# ambika_polivoks.net
KiCad netlist of a schematic drawn in EAGLE
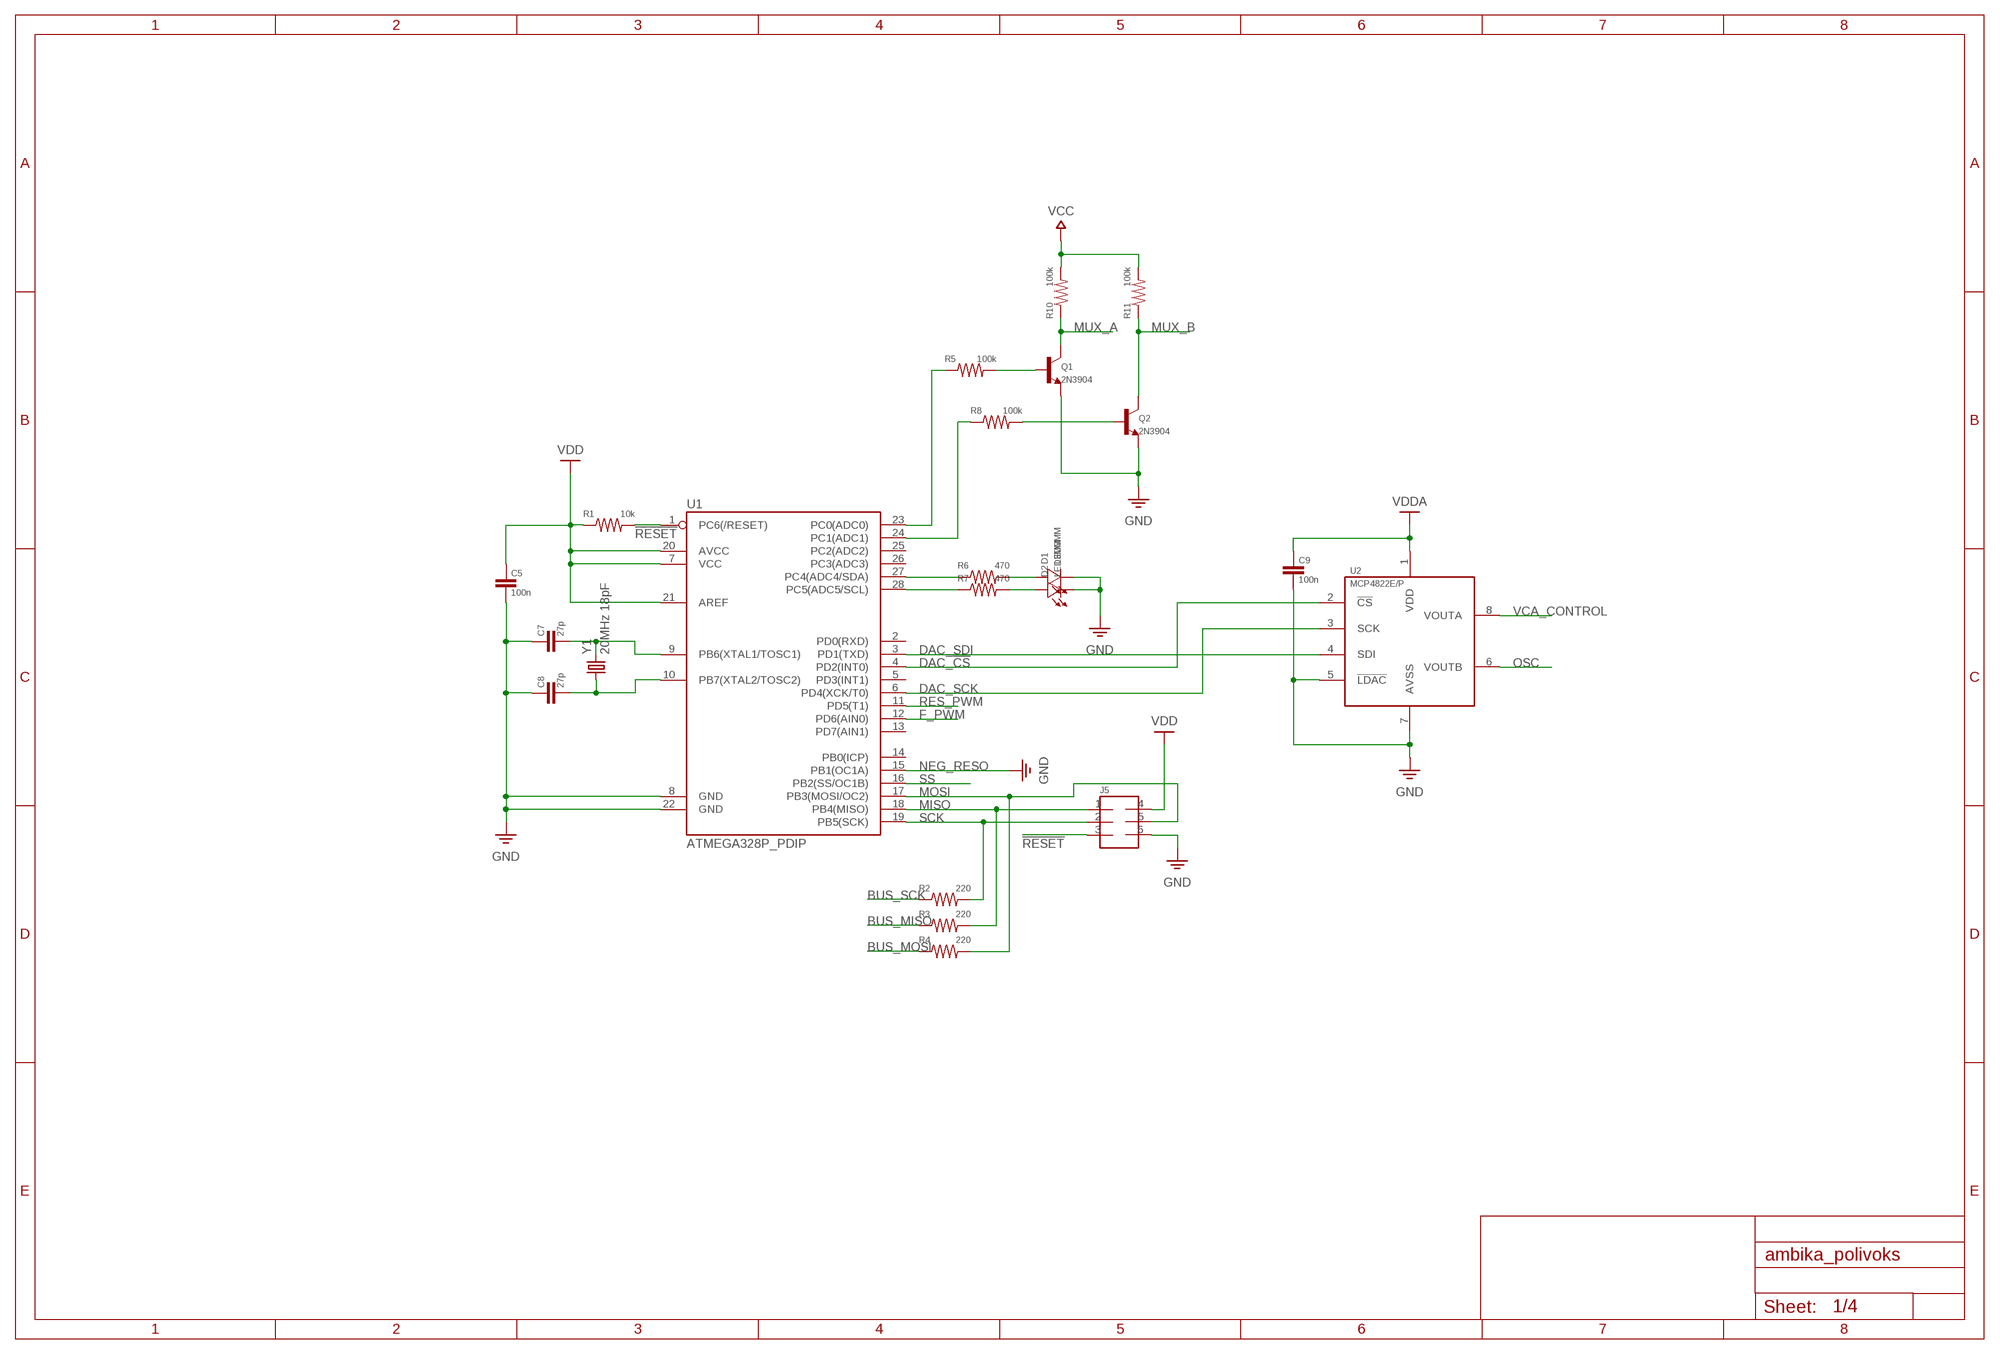
[diagram p0: schematic, sheet 1]
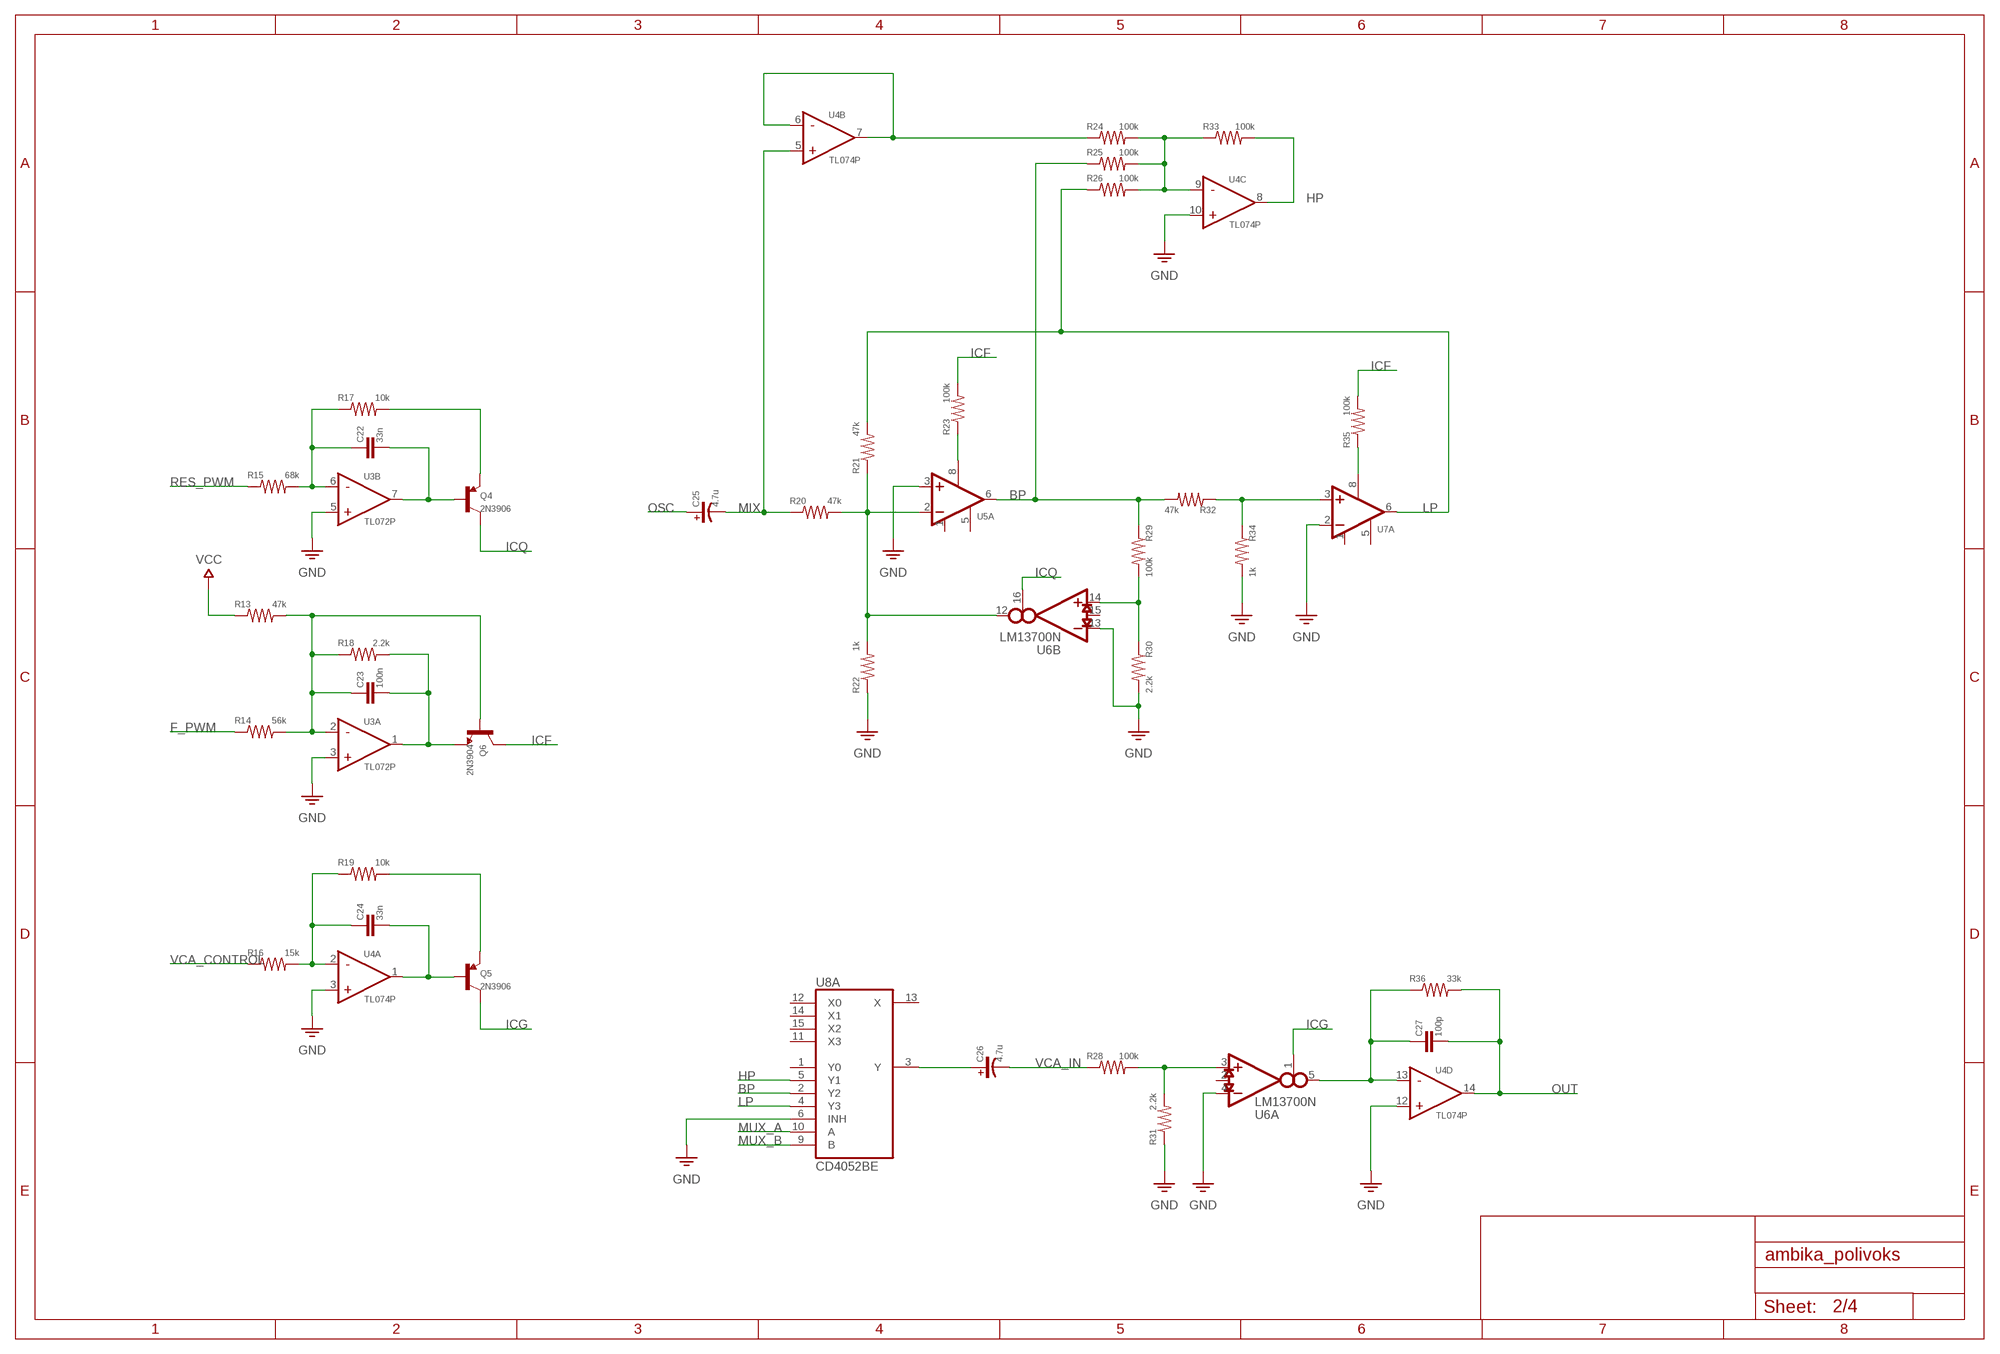
[diagram p1: schematic, sheet 2]
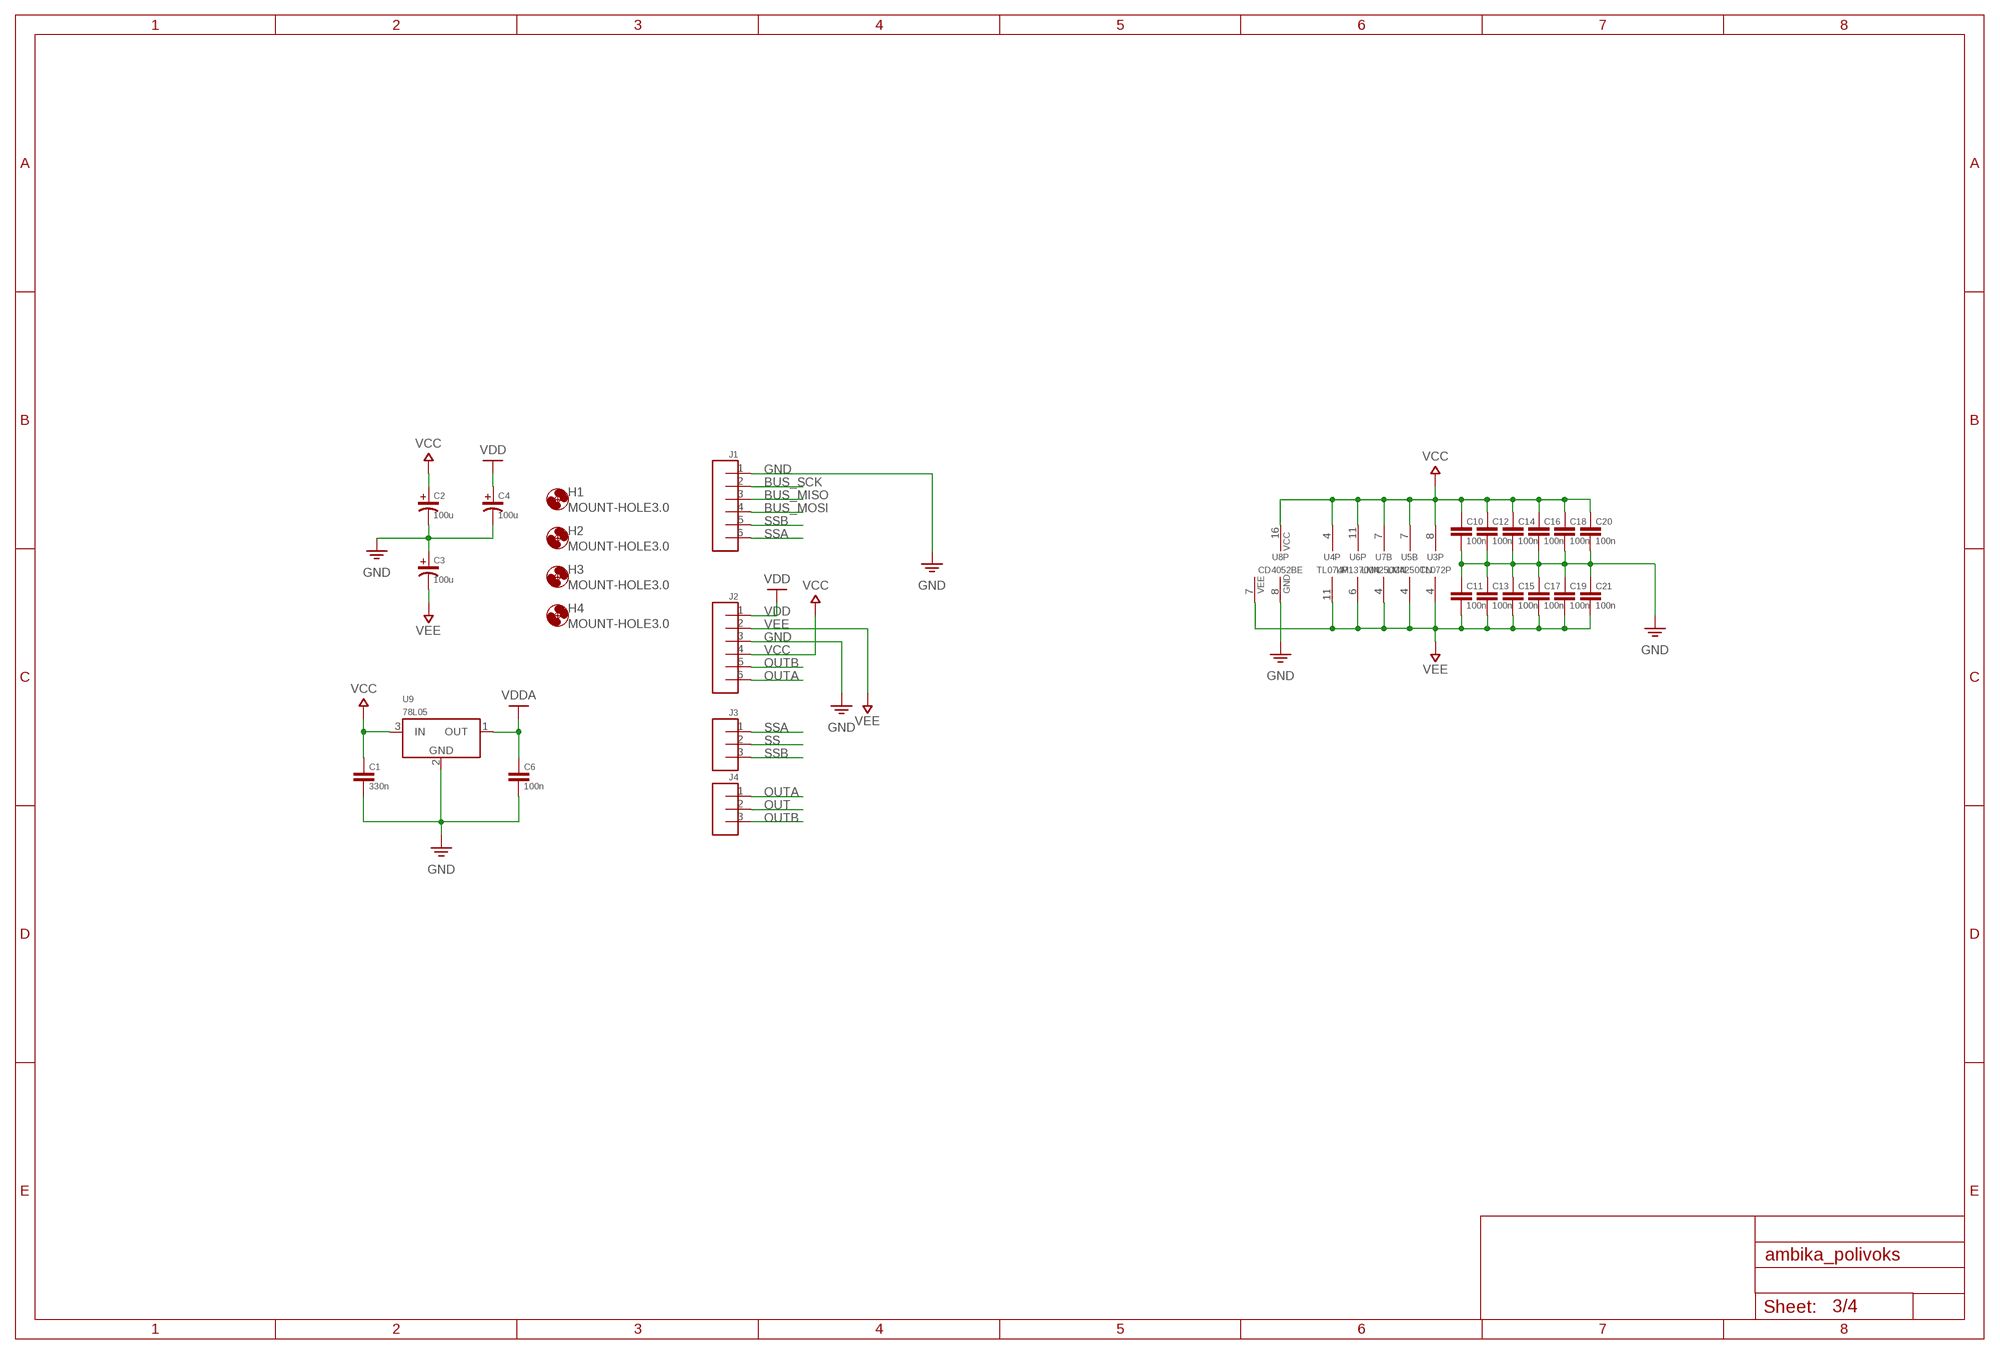
[diagram p2: schematic, sheet 3]
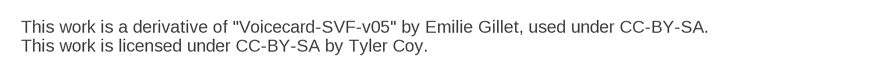
[diagram p3: schematic, sheet 4]

(export (version "E")
  (design (tool "Eeschema 10.0.6"))
  (components
    (comp (ref "C22")
      (value "33n")
      (footprint "eagle-import:CAP_0.1")
      (libsource (lib "eagle-import") (part "CAPACITOR"))
    )
    (comp (ref "C23")
      (value "100n")
      (footprint "eagle-import:CAP_0.1")
      (libsource (lib "eagle-import") (part "CAPACITOR"))
    )
    (comp (ref "C24")
      (value "33n")
      (footprint "eagle-import:CAP_0.1")
      (libsource (lib "eagle-import") (part "CAPACITOR"))
    )
    (comp (ref "C25")
      (value "4.7u")
      (footprint "eagle-import:CAP_ELEC_5MM_2MM_HORZ1")
      (libsource (lib "eagle-import") (part "CAPACITOR_POLARIZED5MM_HORZ1"))
    )
    (comp (ref "C26")
      (value "4.7u")
      (footprint "eagle-import:CAP_ELEC_5MM_2MM_HORZ2")
      (libsource (lib "eagle-import") (part "CAPACITOR_POLARIZED5MM_HORZ2"))
    )
    (comp (ref "C27")
      (value "100p")
      (footprint "eagle-import:CAP_0.1")
      (libsource (lib "eagle-import") (part "CAPACITOR"))
    )
    (comp (ref "Q4")
      (value "2N3906")
      (footprint "eagle-import:TO-92_TRI")
      (libsource (lib "eagle-import") (part "2N3906"))
    )
    (comp (ref "Q5")
      (value "2N3906")
      (footprint "eagle-import:TO-92_TRI")
      (libsource (lib "eagle-import") (part "2N3906"))
    )
    (comp (ref "Q6")
      (value "2N3904")
      (footprint "eagle-import:TO-92_TRI")
      (libsource (lib "eagle-import") (part "2N3904"))
    )
    (comp (ref "R13")
      (value "47k")
      (footprint "eagle-import:RESISTOR_1_4W")
      (libsource (lib "eagle-import") (part "RESISTOR_PTH_1/4W"))
    )
    (comp (ref "R14")
      (value "56k")
      (footprint "eagle-import:RESISTOR_1_4W")
      (libsource (lib "eagle-import") (part "RESISTOR_PTH_1/4W"))
    )
    (comp (ref "R15")
      (value "68k")
      (footprint "eagle-import:RESISTOR_1_4W")
      (libsource (lib "eagle-import") (part "RESISTOR_PTH_1/4W"))
    )
    (comp (ref "R16")
      (value "15k")
      (footprint "eagle-import:RESISTOR_1_4W")
      (libsource (lib "eagle-import") (part "RESISTOR_PTH_1/4W"))
    )
    (comp (ref "R17")
      (value "10k")
      (footprint "eagle-import:RESISTOR_1_4W")
      (libsource (lib "eagle-import") (part "RESISTOR_PTH_1/4W"))
    )
    (comp (ref "R18")
      (value "2.2k")
      (footprint "eagle-import:RESISTOR_1_4W")
      (libsource (lib "eagle-import") (part "RESISTOR_PTH_1/4W"))
    )
    (comp (ref "R19")
      (value "10k")
      (footprint "eagle-import:RESISTOR_1_4W")
      (libsource (lib "eagle-import") (part "RESISTOR_PTH_1/4W"))
    )
    (comp (ref "R20")
      (value "47k")
      (footprint "eagle-import:RESISTOR_1_4W")
      (libsource (lib "eagle-import") (part "RESISTOR_PTH_1/4W"))
    )
    (comp (ref "R21")
      (value "47k")
      (footprint "eagle-import:RESISTOR_1_4W")
      (libsource (lib "eagle-import") (part "RESISTOR_PTH_1/4W"))
    )
    (comp (ref "R22")
      (value "1k")
      (footprint "eagle-import:RESISTOR_1_4W")
      (libsource (lib "eagle-import") (part "RESISTOR_PTH_1/4W"))
    )
    (comp (ref "R23")
      (value "100k")
      (footprint "eagle-import:RESISTOR_1_4W")
      (libsource (lib "eagle-import") (part "RESISTOR_PTH_1/4W"))
    )
    (comp (ref "R24")
      (value "100k")
      (footprint "eagle-import:RESISTOR_1_4W")
      (libsource (lib "eagle-import") (part "RESISTOR_PTH_1/4W"))
    )
    (comp (ref "R25")
      (value "100k")
      (footprint "eagle-import:RESISTOR_1_4W")
      (libsource (lib "eagle-import") (part "RESISTOR_PTH_1/4W"))
    )
    (comp (ref "R26")
      (value "100k")
      (footprint "eagle-import:RESISTOR_1_4W")
      (libsource (lib "eagle-import") (part "RESISTOR_PTH_1/4W"))
    )
    (comp (ref "R28")
      (value "100k")
      (footprint "eagle-import:RESISTOR_1_4W")
      (libsource (lib "eagle-import") (part "RESISTOR_PTH_1/4W"))
    )
    (comp (ref "R29")
      (value "100k")
      (footprint "eagle-import:RESISTOR_1_4W")
      (libsource (lib "eagle-import") (part "RESISTOR_PTH_1/4W"))
    )
    (comp (ref "R30")
      (value "2.2k")
      (footprint "eagle-import:RESISTOR_1_4W")
      (libsource (lib "eagle-import") (part "RESISTOR_PTH_1/4W"))
    )
    (comp (ref "R31")
      (value "2.2k")
      (footprint "eagle-import:RESISTOR_1_4W")
      (libsource (lib "eagle-import") (part "RESISTOR_PTH_1/4W"))
    )
    (comp (ref "R32")
      (value "47k")
      (footprint "eagle-import:RESISTOR_1_4W")
      (libsource (lib "eagle-import") (part "RESISTOR_PTH_1/4W"))
    )
    (comp (ref "R33")
      (value "100k")
      (footprint "eagle-import:RESISTOR_1_4W")
      (libsource (lib "eagle-import") (part "RESISTOR_PTH_1/4W"))
    )
    (comp (ref "R34")
      (value "1k")
      (footprint "eagle-import:RESISTOR_1_4W")
      (libsource (lib "eagle-import") (part "RESISTOR_PTH_1/4W"))
    )
    (comp (ref "R35")
      (value "100k")
      (footprint "eagle-import:RESISTOR_1_4W")
      (libsource (lib "eagle-import") (part "RESISTOR_PTH_1/4W"))
    )
    (comp (ref "R36")
      (value "33k")
      (footprint "eagle-import:RESISTOR_1_4W")
      (libsource (lib "eagle-import") (part "RESISTOR_PTH_1/4W"))
    )
    (comp (ref "U3")
      (value "TL072P")
      (footprint "eagle-import:DIP8")
      (libsource (lib "eagle-import") (part "TL072P"))
    )
    (comp (ref "U4")
      (value "TL074P")
      (footprint "eagle-import:DIP14")
      (libsource (lib "eagle-import") (part "TL074P"))
    )
    (comp (ref "U5")
      (value "LM4250CN")
      (footprint "eagle-import:DIP8")
      (libsource (lib "eagle-import") (part "LM4250CN"))
    )
    (comp (ref "U6")
      (value "LM13700N")
      (footprint "eagle-import:DIP16")
      (libsource (lib "eagle-import") (part "LM13700N"))
    )
    (comp (ref "U7")
      (value "LM4250CN")
      (footprint "eagle-import:DIP8")
      (libsource (lib "eagle-import") (part "LM4250CN"))
    )
    (comp (ref "U8")
      (value "CD4052BE")
      (footprint "eagle-import:DIP16")
      (libsource (lib "eagle-import") (part "CD4052BE"))
    )
    (comp (ref "C5")
      (value "100n")
      (footprint "eagle-import:CAP_0.1")
      (libsource (lib "eagle-import") (part "CAPACITOR"))
    )
    (comp (ref "C7")
      (value "27p")
      (footprint "eagle-import:CAP_0.1")
      (libsource (lib "eagle-import") (part "CAPACITOR"))
    )
    (comp (ref "C8")
      (value "27p")
      (footprint "eagle-import:CAP_0.1")
      (libsource (lib "eagle-import") (part "CAPACITOR"))
    )
    (comp (ref "C9")
      (value "100n")
      (footprint "eagle-import:CAP_0.1")
      (libsource (lib "eagle-import") (part "CAPACITOR"))
    )
    (comp (ref "D1")
      (value "LED3MM")
      (footprint "eagle-import:LED3MM")
      (libsource (lib "eagle-import") (part "LED3MM"))
    )
    (comp (ref "D2")
      (value "LED3MM")
      (footprint "eagle-import:LED3MM")
      (libsource (lib "eagle-import") (part "LED3MM"))
    )
    (comp (ref "J5")
      (value "HEADER_2X3")
      (footprint "eagle-import:HEADER_2X3")
      (libsource (lib "eagle-import") (part "HEADER_2X3"))
    )
    (comp (ref "Q1")
      (value "2N3904")
      (footprint "eagle-import:TO-92_TRI")
      (libsource (lib "eagle-import") (part "2N3904"))
    )
    (comp (ref "Q2")
      (value "2N3904")
      (footprint "eagle-import:TO-92_TRI")
      (libsource (lib "eagle-import") (part "2N3904"))
    )
    (comp (ref "R1")
      (value "10k")
      (footprint "eagle-import:RESISTOR_1_4W")
      (libsource (lib "eagle-import") (part "RESISTOR_PTH_1/4W"))
    )
    (comp (ref "R2")
      (value "220")
      (footprint "eagle-import:RESISTOR_1_4W")
      (libsource (lib "eagle-import") (part "RESISTOR_PTH_1/4W"))
    )
    (comp (ref "R3")
      (value "220")
      (footprint "eagle-import:RESISTOR_1_4W")
      (libsource (lib "eagle-import") (part "RESISTOR_PTH_1/4W"))
    )
    (comp (ref "R4")
      (value "220")
      (footprint "eagle-import:RESISTOR_1_4W")
      (libsource (lib "eagle-import") (part "RESISTOR_PTH_1/4W"))
    )
    (comp (ref "R5")
      (value "100k")
      (footprint "eagle-import:RESISTOR_1_4W")
      (libsource (lib "eagle-import") (part "RESISTOR_PTH_1/4W"))
    )
    (comp (ref "R6")
      (value "470")
      (footprint "eagle-import:RESISTOR_1_4W")
      (libsource (lib "eagle-import") (part "RESISTOR_PTH_1/4W"))
    )
    (comp (ref "R7")
      (value "470")
      (footprint "eagle-import:RESISTOR_1_4W")
      (libsource (lib "eagle-import") (part "RESISTOR_PTH_1/4W"))
    )
    (comp (ref "R8")
      (value "100k")
      (footprint "eagle-import:RESISTOR_1_4W")
      (libsource (lib "eagle-import") (part "RESISTOR_PTH_1/4W"))
    )
    (comp (ref "R10")
      (value "100k")
      (footprint "eagle-import:RESISTOR_1_4W")
      (libsource (lib "eagle-import") (part "RESISTOR_PTH_1/4W"))
    )
    (comp (ref "R11")
      (value "100k")
      (footprint "eagle-import:RESISTOR_1_4W")
      (libsource (lib "eagle-import") (part "RESISTOR_PTH_1/4W"))
    )
    (comp (ref "U1")
      (value "ATMEGA328P_PDIP")
      (footprint "eagle-import:DIP28")
      (libsource (lib "eagle-import") (part "ATMEGA328P_PDIP"))
    )
    (comp (ref "U2")
      (value "MCP4822E/P")
      (footprint "eagle-import:DIP8")
      (libsource (lib "eagle-import") (part "MCP4822E/P"))
    )
    (comp (ref "Y1")
      (value "20MHz 18pF")
      (footprint "eagle-import:HC49US")
      (libsource (lib "eagle-import") (part "CRYSTALHC49US"))
    )
    (comp (ref "C1")
      (value "330n")
      (footprint "eagle-import:CAP_0.1")
      (libsource (lib "eagle-import") (part "CAPACITOR"))
    )
    (comp (ref "C2")
      (value "100u")
      (footprint "eagle-import:CAP_ELEC_6.3MM_2.5MM_HORZ2")
      (libsource (lib "eagle-import") (part "CAPACITOR_POLARIZED6.3MM_HORZ2"))
    )
    (comp (ref "C3")
      (value "100u")
      (footprint "eagle-import:CAP_ELEC_6.3MM_2.5MM_HORZ2")
      (libsource (lib "eagle-import") (part "CAPACITOR_POLARIZED6.3MM_HORZ2"))
    )
    (comp (ref "C4")
      (value "100u")
      (footprint "eagle-import:CAP_ELEC_6.3MM_2.5MM_HORZ2")
      (libsource (lib "eagle-import") (part "CAPACITOR_POLARIZED6.3MM_HORZ2"))
    )
    (comp (ref "C6")
      (value "100n")
      (footprint "eagle-import:CAP_0.1")
      (libsource (lib "eagle-import") (part "CAPACITOR"))
    )
    (comp (ref "C10")
      (value "100n")
      (footprint "eagle-import:CAP_0.1")
      (libsource (lib "eagle-import") (part "CAPACITOR"))
    )
    (comp (ref "C11")
      (value "100n")
      (footprint "eagle-import:CAP_0.1")
      (libsource (lib "eagle-import") (part "CAPACITOR"))
    )
    (comp (ref "C12")
      (value "100n")
      (footprint "eagle-import:CAP_0.1")
      (libsource (lib "eagle-import") (part "CAPACITOR"))
    )
    (comp (ref "C13")
      (value "100n")
      (footprint "eagle-import:CAP_0.1")
      (libsource (lib "eagle-import") (part "CAPACITOR"))
    )
    (comp (ref "C14")
      (value "100n")
      (footprint "eagle-import:CAP_0.1")
      (libsource (lib "eagle-import") (part "CAPACITOR"))
    )
    (comp (ref "C15")
      (value "100n")
      (footprint "eagle-import:CAP_0.1")
      (libsource (lib "eagle-import") (part "CAPACITOR"))
    )
    (comp (ref "C16")
      (value "100n")
      (footprint "eagle-import:CAP_0.1")
      (libsource (lib "eagle-import") (part "CAPACITOR"))
    )
    (comp (ref "C17")
      (value "100n")
      (footprint "eagle-import:CAP_0.1")
      (libsource (lib "eagle-import") (part "CAPACITOR"))
    )
    (comp (ref "C18")
      (value "100n")
      (footprint "eagle-import:CAP_0.1")
      (libsource (lib "eagle-import") (part "CAPACITOR"))
    )
    (comp (ref "C19")
      (value "100n")
      (footprint "eagle-import:CAP_0.1")
      (libsource (lib "eagle-import") (part "CAPACITOR"))
    )
    (comp (ref "C20")
      (value "100n")
      (footprint "eagle-import:CAP_0.1")
      (libsource (lib "eagle-import") (part "CAPACITOR"))
    )
    (comp (ref "C21")
      (value "100n")
      (footprint "eagle-import:CAP_0.1")
      (libsource (lib "eagle-import") (part "CAPACITOR"))
    )
    (comp (ref "H1")
      (value "MOUNT-HOLE3.0")
      (footprint "eagle-import:3,0")
      (libsource (lib "eagle-import") (part "MOUNT-HOLE3.0"))
    )
    (comp (ref "H2")
      (value "MOUNT-HOLE3.0")
      (footprint "eagle-import:3,0")
      (libsource (lib "eagle-import") (part "MOUNT-HOLE3.0"))
    )
    (comp (ref "H3")
      (value "MOUNT-HOLE3.0")
      (footprint "eagle-import:3,0")
      (libsource (lib "eagle-import") (part "MOUNT-HOLE3.0"))
    )
    (comp (ref "H4")
      (value "MOUNT-HOLE3.0")
      (footprint "eagle-import:3,0")
      (libsource (lib "eagle-import") (part "MOUNT-HOLE3.0"))
    )
    (comp (ref "J1")
      (value "HEADER_1X6")
      (footprint "eagle-import:HEADER_1X6")
      (libsource (lib "eagle-import") (part "HEADER_1X6"))
    )
    (comp (ref "J2")
      (value "HEADER_1X6")
      (footprint "eagle-import:HEADER_1X6")
      (libsource (lib "eagle-import") (part "HEADER_1X6"))
    )
    (comp (ref "J3")
      (value "HEADER_1X3")
      (footprint "eagle-import:HEADER_1X3")
      (libsource (lib "eagle-import") (part "HEADER_1X3"))
    )
    (comp (ref "J4")
      (value "HEADER_1X3")
      (footprint "eagle-import:HEADER_1X3")
      (libsource (lib "eagle-import") (part "HEADER_1X3"))
    )
    (comp (ref "U9")
      (value "78L05")
      (footprint "eagle-import:TO-92_TRI")
      (libsource (lib "eagle-import") (part "78L05"))
    )
  )
  (nets
    (net (code "1") (name "BP") (class "Default")
      (node (ref "R25") (pin "P$1") (pinfunction "1_P$1") (pintype "passive"))
      (node (ref "R29") (pin "P$1") (pinfunction "1_P$1") (pintype "passive"))
      (node (ref "R32") (pin "P$2") (pinfunction "2_P$2") (pintype "passive"))
      (node (ref "U5") (pin "6") (pinfunction "OUTPUT_6") (pintype "bidirectional"))
      (node (ref "U8") (pin "2") (pinfunction "Y2_2") (pintype "bidirectional"))
    )
    (net (code "2") (name "BUS_MISO") (class "Default")
      (node (ref "J1") (pin "3") (pinfunction "3_3") (pintype "bidirectional"))
      (node (ref "R3") (pin "P$1") (pinfunction "1_P$1") (pintype "passive"))
    )
    (net (code "3") (name "BUS_MOSI") (class "Default")
      (node (ref "J1") (pin "4") (pinfunction "4_4") (pintype "bidirectional"))
      (node (ref "R4") (pin "P$1") (pinfunction "1_P$1") (pintype "passive"))
    )
    (net (code "4") (name "BUS_SCK") (class "Default")
      (node (ref "J1") (pin "2") (pinfunction "2_2") (pintype "bidirectional"))
      (node (ref "R2") (pin "P$1") (pinfunction "1_P$1") (pintype "passive"))
    )
    (net (code "5") (name "DAC_SCK") (class "Default")
      (node (ref "U1") (pin "6") (pinfunction "PD4(XCK/T0)_6") (pintype "bidirectional"))
      (node (ref "U2") (pin "3") (pinfunction "SCK_3") (pintype "input"))
    )
    (net (code "6") (name "DAC_SDI") (class "Default")
      (node (ref "U1") (pin "3") (pinfunction "PD1(TXD)_3") (pintype "bidirectional"))
      (node (ref "U2") (pin "4") (pinfunction "SDI_4") (pintype "input"))
    )
    (net (code "7") (name "DAC_~{CS}") (class "Default")
      (node (ref "U1") (pin "4") (pinfunction "PD2(INT0)_4") (pintype "bidirectional"))
      (node (ref "U2") (pin "2") (pinfunction "~{CS}_2") (pintype "input"))
    )
    (net (code "8") (name "F_PWM") (class "Default")
      (node (ref "R14") (pin "P$1") (pinfunction "1_P$1") (pintype "passive"))
      (node (ref "U1") (pin "12") (pinfunction "PD6(AIN0)_12") (pintype "bidirectional"))
    )
    (net (code "9") (name "GND") (class "Default")
      (node (ref "C1") (pin "2") (pinfunction "2_2") (pintype "passive"))
      (node (ref "C10") (pin "2") (pinfunction "2_2") (pintype "passive"))
      (node (ref "C11") (pin "1") (pinfunction "1_1") (pintype "passive"))
      (node (ref "C12") (pin "2") (pinfunction "2_2") (pintype "passive"))
      (node (ref "C13") (pin "1") (pinfunction "1_1") (pintype "passive"))
      (node (ref "C14") (pin "2") (pinfunction "2_2") (pintype "passive"))
      (node (ref "C15") (pin "1") (pinfunction "1_1") (pintype "passive"))
      (node (ref "C16") (pin "2") (pinfunction "2_2") (pintype "passive"))
      (node (ref "C17") (pin "1") (pinfunction "1_1") (pintype "passive"))
      (node (ref "C18") (pin "2") (pinfunction "2_2") (pintype "passive"))
      (node (ref "C19") (pin "1") (pinfunction "1_1") (pintype "passive"))
      (node (ref "C2") (pin "C") (pinfunction "C_C") (pintype "passive"))
      (node (ref "C20") (pin "2") (pinfunction "2_2") (pintype "passive"))
      (node (ref "C21") (pin "1") (pinfunction "1_1") (pintype "passive"))
      (node (ref "C3") (pin "A") (pinfunction "A_A") (pintype "passive"))
      (node (ref "C4") (pin "C") (pinfunction "C_C") (pintype "passive"))
      (node (ref "C5") (pin "2") (pinfunction "2_2") (pintype "passive"))
      (node (ref "C6") (pin "2") (pinfunction "2_2") (pintype "passive"))
      (node (ref "C7") (pin "1") (pinfunction "1_1") (pintype "passive"))
      (node (ref "C8") (pin "1") (pinfunction "1_1") (pintype "passive"))
      (node (ref "C9") (pin "2") (pinfunction "2_2") (pintype "passive"))
      (node (ref "D1") (pin "K") (pinfunction "K_K") (pintype "bidirectional"))
      (node (ref "D2") (pin "K") (pinfunction "K_K") (pintype "bidirectional"))
      (node (ref "J1") (pin "1") (pinfunction "1_1") (pintype "bidirectional"))
      (node (ref "J2") (pin "3") (pinfunction "3_3") (pintype "bidirectional"))
      (node (ref "J5") (pin "6") (pinfunction "6_6") (pintype "bidirectional"))
      (node (ref "Q1") (pin "1") (pinfunction "E_1") (pintype "bidirectional"))
      (node (ref "Q2") (pin "1") (pinfunction "E_1") (pintype "bidirectional"))
      (node (ref "R22") (pin "P$1") (pinfunction "1_P$1") (pintype "passive"))
      (node (ref "R30") (pin "P$2") (pinfunction "2_P$2") (pintype "passive"))
      (node (ref "R31") (pin "P$1") (pinfunction "1_P$1") (pintype "passive"))
      (node (ref "R34") (pin "P$2") (pinfunction "2_P$2") (pintype "passive"))
      (node (ref "U1") (pin "15") (pinfunction "PB1(OC1A)_15") (pintype "bidirectional"))
      (node (ref "U1") (pin "22") (pinfunction "GND_22") (pintype "bidirectional"))
      (node (ref "U1") (pin "8") (pinfunction "GND_8") (pintype "bidirectional"))
      (node (ref "U2") (pin "5") (pinfunction "~{LDAC}_5") (pintype "input"))
      (node (ref "U2") (pin "7") (pinfunction "AVSS_7") (pintype "power_in"))
      (node (ref "U3") (pin "3") (pinfunction "IN+_3") (pintype "input"))
      (node (ref "U3") (pin "5") (pinfunction "IN+_5") (pintype "input"))
      (node (ref "U4") (pin "10") (pinfunction "IN+_10") (pintype "input"))
      (node (ref "U4") (pin "12") (pinfunction "IN+_12") (pintype "input"))
      (node (ref "U4") (pin "3") (pinfunction "IN+_3") (pintype "input"))
      (node (ref "U5") (pin "3") (pinfunction "V+_3") (pintype "bidirectional"))
      (node (ref "U6") (pin "13") (pinfunction "-_13") (pintype "bidirectional"))
      (node (ref "U6") (pin "4") (pinfunction "-_4") (pintype "bidirectional"))
      (node (ref "U7") (pin "2") (pinfunction "V-_2") (pintype "bidirectional"))
      (node (ref "U8") (pin "6") (pinfunction "INH_6") (pintype "input"))
      (node (ref "U8") (pin "8") (pinfunction "GND_8") (pintype "bidirectional"))
      (node (ref "U9") (pin "2") (pinfunction "GND_2") (pintype "bidirectional"))
    )
    (net (code "10") (name "HP") (class "Default")
      (node (ref "R33") (pin "P$2") (pinfunction "2_P$2") (pintype "passive"))
      (node (ref "U4") (pin "8") (pinfunction "OUT_8") (pintype "output"))
      (node (ref "U8") (pin "5") (pinfunction "Y1_5") (pintype "bidirectional"))
    )
    (net (code "11") (name "ICF") (class "Default")
      (node (ref "Q6") (pin "3") (pinfunction "C_3") (pintype "bidirectional"))
      (node (ref "R23") (pin "P$2") (pinfunction "2_P$2") (pintype "passive"))
      (node (ref "R35") (pin "P$2") (pinfunction "2_P$2") (pintype "passive"))
    )
    (net (code "12") (name "ICG") (class "Default")
      (node (ref "Q5") (pin "3") (pinfunction "C_3") (pintype "bidirectional"))
      (node (ref "U6") (pin "1") (pinfunction "AMP_BIAS_1") (pintype "bidirectional"))
    )
    (net (code "13") (name "ICQ") (class "Default")
      (node (ref "Q4") (pin "3") (pinfunction "C_3") (pintype "bidirectional"))
      (node (ref "U6") (pin "16") (pinfunction "AMP_BIAS_16") (pintype "bidirectional"))
    )
    (net (code "14") (name "LP") (class "Default")
      (node (ref "R21") (pin "P$2") (pinfunction "2_P$2") (pintype "passive"))
      (node (ref "R26") (pin "P$1") (pinfunction "1_P$1") (pintype "passive"))
      (node (ref "U7") (pin "6") (pinfunction "OUTPUT_6") (pintype "bidirectional"))
      (node (ref "U8") (pin "4") (pinfunction "Y3_4") (pintype "bidirectional"))
    )
    (net (code "15") (name "MISO") (class "Default")
      (node (ref "J5") (pin "1") (pinfunction "1_1") (pintype "bidirectional"))
      (node (ref "R3") (pin "P$2") (pinfunction "2_P$2") (pintype "passive"))
      (node (ref "U1") (pin "18") (pinfunction "PB4(MISO)_18") (pintype "bidirectional"))
    )
    (net (code "16") (name "MIX") (class "Default")
      (node (ref "C25") (pin "C") (pinfunction "C_C") (pintype "passive"))
      (node (ref "R20") (pin "P$1") (pinfunction "1_P$1") (pintype "passive"))
      (node (ref "U4") (pin "5") (pinfunction "IN+_5") (pintype "input"))
    )
    (net (code "17") (name "MOSI") (class "Default")
      (node (ref "J5") (pin "5") (pinfunction "5_5") (pintype "bidirectional"))
      (node (ref "R4") (pin "P$2") (pinfunction "2_P$2") (pintype "passive"))
      (node (ref "U1") (pin "17") (pinfunction "PB3(MOSI/OC2)_17") (pintype "bidirectional"))
    )
    (net (code "18") (name "MUX_A") (class "Default")
      (node (ref "Q1") (pin "3") (pinfunction "C_3") (pintype "bidirectional"))
      (node (ref "R10") (pin "P$1") (pinfunction "1_P$1") (pintype "passive"))
      (node (ref "U8") (pin "10") (pinfunction "A_10") (pintype "input"))
    )
    (net (code "19") (name "MUX_B") (class "Default")
      (node (ref "Q2") (pin "3") (pinfunction "C_3") (pintype "bidirectional"))
      (node (ref "R11") (pin "P$1") (pinfunction "1_P$1") (pintype "passive"))
      (node (ref "U8") (pin "9") (pinfunction "B_9") (pintype "input"))
    )
    (net (code "20") (name "Net-(Q1-B)") (class "Default")
      (node (ref "Q1") (pin "2") (pinfunction "B_2") (pintype "bidirectional"))
      (node (ref "R5") (pin "P$2") (pinfunction "2_P$2") (pintype "passive"))
    )
    (net (code "21") (name "Net-(Q2-B)") (class "Default")
      (node (ref "Q2") (pin "2") (pinfunction "B_2") (pintype "bidirectional"))
      (node (ref "R8") (pin "P$2") (pinfunction "2_P$2") (pintype "passive"))
    )
    (net (code "22") (name "Net-(Q4-B)") (class "Default")
      (node (ref "C22") (pin "2") (pinfunction "2_2") (pintype "passive"))
      (node (ref "Q4") (pin "2") (pinfunction "B_2") (pintype "bidirectional"))
      (node (ref "U3") (pin "7") (pinfunction "OUT_7") (pintype "output"))
    )
    (net (code "23") (name "Net-(Q4-E)") (class "Default")
      (node (ref "Q4") (pin "1") (pinfunction "E_1") (pintype "bidirectional"))
      (node (ref "R17") (pin "P$2") (pinfunction "2_P$2") (pintype "passive"))
    )
    (net (code "24") (name "Net-(Q5-B)") (class "Default")
      (node (ref "C24") (pin "2") (pinfunction "2_2") (pintype "passive"))
      (node (ref "Q5") (pin "2") (pinfunction "B_2") (pintype "bidirectional"))
      (node (ref "U4") (pin "1") (pinfunction "OUT_1") (pintype "output"))
    )
    (net (code "25") (name "Net-(Q5-E)") (class "Default")
      (node (ref "Q5") (pin "1") (pinfunction "E_1") (pintype "bidirectional"))
      (node (ref "R19") (pin "P$2") (pinfunction "2_P$2") (pintype "passive"))
    )
    (net (code "26") (name "Net-(Q6-B)") (class "Default")
      (node (ref "C23") (pin "1") (pinfunction "1_1") (pintype "passive"))
      (node (ref "Q6") (pin "2") (pinfunction "B_2") (pintype "bidirectional"))
      (node (ref "R13") (pin "P$2") (pinfunction "2_P$2") (pintype "passive"))
      (node (ref "R14") (pin "P$2") (pinfunction "2_P$2") (pintype "passive"))
      (node (ref "R18") (pin "P$1") (pinfunction "1_P$1") (pintype "passive"))
      (node (ref "U3") (pin "2") (pinfunction "IN-_2") (pintype "input"))
    )
    (net (code "27") (name "Net-(Q6-E)") (class "Default")
      (node (ref "C23") (pin "2") (pinfunction "2_2") (pintype "passive"))
      (node (ref "Q6") (pin "1") (pinfunction "E_1") (pintype "bidirectional"))
      (node (ref "R18") (pin "P$2") (pinfunction "2_P$2") (pintype "passive"))
      (node (ref "U3") (pin "1") (pinfunction "OUT_1") (pintype "output"))
    )
    (net (code "28") (name "Net-(R5-1)") (class "Default")
      (node (ref "R5") (pin "P$1") (pinfunction "1_P$1") (pintype "passive"))
      (node (ref "U1") (pin "23") (pinfunction "PC0(ADC0)_23") (pintype "bidirectional"))
    )
    (net (code "29") (name "Net-(R6-1)") (class "Default")
      (node (ref "R6") (pin "P$1") (pinfunction "1_P$1") (pintype "passive"))
      (node (ref "U1") (pin "27") (pinfunction "PC4(ADC4/SDA)_27") (pintype "bidirectional"))
    )
    (net (code "30") (name "Net-(R6-2)") (class "Default")
      (node (ref "D1") (pin "A") (pinfunction "A_A") (pintype "bidirectional"))
      (node (ref "R6") (pin "P$2") (pinfunction "2_P$2") (pintype "passive"))
    )
    (net (code "31") (name "Net-(R7-1)") (class "Default")
      (node (ref "R7") (pin "P$1") (pinfunction "1_P$1") (pintype "passive"))
      (node (ref "U1") (pin "28") (pinfunction "PC5(ADC5/SCL)_28") (pintype "bidirectional"))
    )
    (net (code "32") (name "Net-(R7-2)") (class "Default")
      (node (ref "D2") (pin "A") (pinfunction "A_A") (pintype "bidirectional"))
      (node (ref "R7") (pin "P$2") (pinfunction "2_P$2") (pintype "passive"))
    )
    (net (code "33") (name "Net-(R8-1)") (class "Default")
      (node (ref "R8") (pin "P$1") (pinfunction "1_P$1") (pintype "passive"))
      (node (ref "U1") (pin "24") (pinfunction "PC1(ADC1)_24") (pintype "bidirectional"))
    )
    (net (code "34") (name "Net-(R15-2)") (class "Default")
      (node (ref "C22") (pin "1") (pinfunction "1_1") (pintype "passive"))
      (node (ref "R15") (pin "P$2") (pinfunction "2_P$2") (pintype "passive"))
      (node (ref "R17") (pin "P$1") (pinfunction "1_P$1") (pintype "passive"))
      (node (ref "U3") (pin "6") (pinfunction "IN-_6") (pintype "input"))
    )
    (net (code "35") (name "Net-(R16-2)") (class "Default")
      (node (ref "C24") (pin "1") (pinfunction "1_1") (pintype "passive"))
      (node (ref "R16") (pin "P$2") (pinfunction "2_P$2") (pintype "passive"))
      (node (ref "R19") (pin "P$1") (pinfunction "1_P$1") (pintype "passive"))
      (node (ref "U4") (pin "2") (pinfunction "IN-_2") (pintype "input"))
    )
    (net (code "36") (name "Net-(R20-2)") (class "Default")
      (node (ref "R20") (pin "P$2") (pinfunction "2_P$2") (pintype "passive"))
      (node (ref "R21") (pin "P$1") (pinfunction "1_P$1") (pintype "passive"))
      (node (ref "R22") (pin "P$2") (pinfunction "2_P$2") (pintype "passive"))
      (node (ref "U5") (pin "2") (pinfunction "V-_2") (pintype "bidirectional"))
      (node (ref "U6") (pin "12") (pinfunction "OUTPUT_12") (pintype "bidirectional"))
    )
    (net (code "37") (name "Net-(R23-1)") (class "Default")
      (node (ref "R23") (pin "P$1") (pinfunction "1_P$1") (pintype "passive"))
      (node (ref "U5") (pin "8") (pinfunction "SET_8") (pintype "bidirectional"))
    )
    (net (code "38") (name "Net-(R24-1)") (class "Default")
      (node (ref "R24") (pin "P$1") (pinfunction "1_P$1") (pintype "passive"))
      (node (ref "U4") (pin "6") (pinfunction "IN-_6") (pintype "input"))
      (node (ref "U4") (pin "7") (pinfunction "OUT_7") (pintype "output"))
    )
    (net (code "39") (name "Net-(R24-2)") (class "Default")
      (node (ref "R24") (pin "P$2") (pinfunction "2_P$2") (pintype "passive"))
      (node (ref "R25") (pin "P$2") (pinfunction "2_P$2") (pintype "passive"))
      (node (ref "R26") (pin "P$2") (pinfunction "2_P$2") (pintype "passive"))
      (node (ref "R33") (pin "P$1") (pinfunction "1_P$1") (pintype "passive"))
      (node (ref "U4") (pin "9") (pinfunction "IN-_9") (pintype "input"))
    )
    (net (code "40") (name "Net-(R28-2)") (class "Default")
      (node (ref "R28") (pin "P$2") (pinfunction "2_P$2") (pintype "passive"))
      (node (ref "R31") (pin "P$2") (pinfunction "2_P$2") (pintype "passive"))
      (node (ref "U6") (pin "3") (pinfunction "+_3") (pintype "bidirectional"))
    )
    (net (code "41") (name "Net-(R29-2)") (class "Default")
      (node (ref "R29") (pin "P$2") (pinfunction "2_P$2") (pintype "passive"))
      (node (ref "R30") (pin "P$1") (pinfunction "1_P$1") (pintype "passive"))
      (node (ref "U6") (pin "14") (pinfunction "+_14") (pintype "bidirectional"))
    )
    (net (code "42") (name "Net-(R32-1)") (class "Default")
      (node (ref "R32") (pin "P$1") (pinfunction "1_P$1") (pintype "passive"))
      (node (ref "R34") (pin "P$1") (pinfunction "1_P$1") (pintype "passive"))
      (node (ref "U7") (pin "3") (pinfunction "V+_3") (pintype "bidirectional"))
    )
    (net (code "43") (name "Net-(R35-1)") (class "Default")
      (node (ref "R35") (pin "P$1") (pinfunction "1_P$1") (pintype "passive"))
      (node (ref "U7") (pin "8") (pinfunction "SET_8") (pintype "bidirectional"))
    )
    (net (code "44") (name "Net-(R36-1)") (class "Default")
      (node (ref "C27") (pin "1") (pinfunction "1_1") (pintype "passive"))
      (node (ref "R36") (pin "P$1") (pinfunction "1_P$1") (pintype "passive"))
      (node (ref "U4") (pin "13") (pinfunction "IN-_13") (pintype "input"))
      (node (ref "U6") (pin "5") (pinfunction "OUTPUT_5") (pintype "bidirectional"))
    )
    (net (code "45") (name "Net-(U1-PB6(XTAL1{slash}TOSC1))") (class "Default")
      (node (ref "C7") (pin "2") (pinfunction "2_2") (pintype "passive"))
      (node (ref "U1") (pin "9") (pinfunction "PB6(XTAL1/TOSC1)_9") (pintype "bidirectional"))
      (node (ref "Y1") (pin "2") (pinfunction "2_2") (pintype "passive"))
    )
    (net (code "46") (name "Net-(U1-PB7(XTAL2{slash}TOSC2))") (class "Default")
      (node (ref "C8") (pin "2") (pinfunction "2_2") (pintype "passive"))
      (node (ref "U1") (pin "10") (pinfunction "PB7(XTAL2/TOSC2)_10") (pintype "bidirectional"))
      (node (ref "Y1") (pin "1") (pinfunction "1_1") (pintype "passive"))
    )
    (net (code "47") (name "Net-(U8A-Y)") (class "Default")
      (node (ref "C26") (pin "A") (pinfunction "A_A") (pintype "passive"))
      (node (ref "U8") (pin "3") (pinfunction "Y_3") (pintype "bidirectional"))
    )
    (net (code "48") (name "OSC") (class "Default")
      (node (ref "C25") (pin "A") (pinfunction "A_A") (pintype "passive"))
      (node (ref "U2") (pin "6") (pinfunction "VOUTB_6") (pintype "output"))
    )
    (net (code "49") (name "OUT") (class "Default")
      (node (ref "C27") (pin "2") (pinfunction "2_2") (pintype "passive"))
      (node (ref "J4") (pin "2") (pinfunction "2_2") (pintype "bidirectional"))
      (node (ref "R36") (pin "P$2") (pinfunction "2_P$2") (pintype "passive"))
      (node (ref "U4") (pin "14") (pinfunction "OUT_14") (pintype "output"))
    )
    (net (code "50") (name "OUTA") (class "Default")
      (node (ref "J2") (pin "6") (pinfunction "6_6") (pintype "bidirectional"))
      (node (ref "J4") (pin "1") (pinfunction "1_1") (pintype "bidirectional"))
    )
    (net (code "51") (name "OUTB") (class "Default")
      (node (ref "J2") (pin "5") (pinfunction "5_5") (pintype "bidirectional"))
      (node (ref "J4") (pin "3") (pinfunction "3_3") (pintype "bidirectional"))
    )
    (net (code "52") (name "RES_PWM") (class "Default")
      (node (ref "R15") (pin "P$1") (pinfunction "1_P$1") (pintype "passive"))
      (node (ref "U1") (pin "11") (pinfunction "PD5(T1)_11") (pintype "bidirectional"))
    )
    (net (code "53") (name "SCK") (class "Default")
      (node (ref "J5") (pin "2") (pinfunction "2_2") (pintype "bidirectional"))
      (node (ref "R2") (pin "P$2") (pinfunction "2_P$2") (pintype "passive"))
      (node (ref "U1") (pin "19") (pinfunction "PB5(SCK)_19") (pintype "bidirectional"))
    )
    (net (code "54") (name "SS") (class "Default")
      (node (ref "J3") (pin "2") (pinfunction "2_2") (pintype "bidirectional"))
      (node (ref "U1") (pin "16") (pinfunction "PB2(SS/OC1B)_16") (pintype "bidirectional"))
    )
    (net (code "55") (name "SSA") (class "Default")
      (node (ref "J1") (pin "6") (pinfunction "6_6") (pintype "bidirectional"))
      (node (ref "J3") (pin "1") (pinfunction "1_1") (pintype "bidirectional"))
    )
    (net (code "56") (name "SSB") (class "Default")
      (node (ref "J1") (pin "5") (pinfunction "5_5") (pintype "bidirectional"))
      (node (ref "J3") (pin "3") (pinfunction "3_3") (pintype "bidirectional"))
    )
    (net (code "57") (name "VCA_CONTROL") (class "Default")
      (node (ref "R16") (pin "P$1") (pinfunction "1_P$1") (pintype "passive"))
      (node (ref "U2") (pin "8") (pinfunction "VOUTA_8") (pintype "output"))
    )
    (net (code "58") (name "VCA_IN") (class "Default")
      (node (ref "C26") (pin "C") (pinfunction "C_C") (pintype "passive"))
      (node (ref "R28") (pin "P$1") (pinfunction "1_P$1") (pintype "passive"))
    )
    (net (code "59") (name "VCC") (class "Default")
      (node (ref "C1") (pin "1") (pinfunction "1_1") (pintype "passive"))
      (node (ref "C10") (pin "1") (pinfunction "1_1") (pintype "passive"))
      (node (ref "C12") (pin "1") (pinfunction "1_1") (pintype "passive"))
      (node (ref "C14") (pin "1") (pinfunction "1_1") (pintype "passive"))
      (node (ref "C16") (pin "1") (pinfunction "1_1") (pintype "passive"))
      (node (ref "C18") (pin "1") (pinfunction "1_1") (pintype "passive"))
      (node (ref "C2") (pin "A") (pinfunction "A_A") (pintype "passive"))
      (node (ref "C20") (pin "1") (pinfunction "1_1") (pintype "passive"))
      (node (ref "J2") (pin "4") (pinfunction "4_4") (pintype "bidirectional"))
      (node (ref "R10") (pin "P$2") (pinfunction "2_P$2") (pintype "passive"))
      (node (ref "R11") (pin "P$2") (pinfunction "2_P$2") (pintype "passive"))
      (node (ref "R13") (pin "P$1") (pinfunction "1_P$1") (pintype "passive"))
      (node (ref "U3") (pin "8") (pinfunction "VCC_8") (pintype "bidirectional"))
      (node (ref "U4") (pin "4") (pinfunction "VCC_4") (pintype "bidirectional"))
      (node (ref "U5") (pin "7") (pinfunction "VCC_7") (pintype "bidirectional"))
      (node (ref "U6") (pin "11") (pinfunction "VCC_11") (pintype "bidirectional"))
      (node (ref "U7") (pin "7") (pinfunction "VCC_7") (pintype "bidirectional"))
      (node (ref "U8") (pin "16") (pinfunction "VCC_16") (pintype "bidirectional"))
      (node (ref "U9") (pin "3") (pinfunction "IN_3") (pintype "bidirectional"))
    )
    (net (code "60") (name "VDD") (class "Default")
      (node (ref "C4") (pin "A") (pinfunction "A_A") (pintype "passive"))
      (node (ref "C5") (pin "1") (pinfunction "1_1") (pintype "passive"))
      (node (ref "J2") (pin "1") (pinfunction "1_1") (pintype "bidirectional"))
      (node (ref "J5") (pin "4") (pinfunction "4_4") (pintype "bidirectional"))
      (node (ref "R1") (pin "P$1") (pinfunction "1_P$1") (pintype "passive"))
      (node (ref "U1") (pin "20") (pinfunction "AVCC_20") (pintype "bidirectional"))
      (node (ref "U1") (pin "21") (pinfunction "AREF_21") (pintype "bidirectional"))
      (node (ref "U1") (pin "7") (pinfunction "VCC_7") (pintype "bidirectional"))
    )
    (net (code "61") (name "VDDA") (class "Default")
      (node (ref "C6") (pin "1") (pinfunction "1_1") (pintype "passive"))
      (node (ref "C9") (pin "1") (pinfunction "1_1") (pintype "passive"))
      (node (ref "U2") (pin "1") (pinfunction "VDD_1") (pintype "power_in"))
      (node (ref "U9") (pin "1") (pinfunction "OUT_1") (pintype "bidirectional"))
    )
    (net (code "62") (name "VEE") (class "Default")
      (node (ref "C11") (pin "2") (pinfunction "2_2") (pintype "passive"))
      (node (ref "C13") (pin "2") (pinfunction "2_2") (pintype "passive"))
      (node (ref "C15") (pin "2") (pinfunction "2_2") (pintype "passive"))
      (node (ref "C17") (pin "2") (pinfunction "2_2") (pintype "passive"))
      (node (ref "C19") (pin "2") (pinfunction "2_2") (pintype "passive"))
      (node (ref "C21") (pin "2") (pinfunction "2_2") (pintype "passive"))
      (node (ref "C3") (pin "C") (pinfunction "C_C") (pintype "passive"))
      (node (ref "J2") (pin "2") (pinfunction "2_2") (pintype "bidirectional"))
      (node (ref "U3") (pin "4") (pinfunction "VEE_4") (pintype "bidirectional"))
      (node (ref "U4") (pin "11") (pinfunction "VEE_11") (pintype "bidirectional"))
      (node (ref "U5") (pin "4") (pinfunction "VEE_4") (pintype "bidirectional"))
      (node (ref "U6") (pin "6") (pinfunction "VEE_6") (pintype "bidirectional"))
      (node (ref "U7") (pin "4") (pinfunction "VEE_4") (pintype "bidirectional"))
      (node (ref "U8") (pin "7") (pinfunction "VEE_7") (pintype "bidirectional"))
    )
    (net (code "63") (name "unconnected-(U1-PB0(ICP)-Pad14)") (class "Default")
      (node (ref "U1") (pin "14") (pinfunction "PB0(ICP)_14") (pintype "bidirectional"))
    )
    (net (code "64") (name "unconnected-(U1-PC2(ADC2)-Pad25)") (class "Default")
      (node (ref "U1") (pin "25") (pinfunction "PC2(ADC2)_25") (pintype "bidirectional"))
    )
    (net (code "65") (name "unconnected-(U1-PC3(ADC3)-Pad26)") (class "Default")
      (node (ref "U1") (pin "26") (pinfunction "PC3(ADC3)_26") (pintype "bidirectional"))
    )
    (net (code "66") (name "unconnected-(U1-PD0(RXD)-Pad2)") (class "Default")
      (node (ref "U1") (pin "2") (pinfunction "PD0(RXD)_2") (pintype "bidirectional"))
    )
    (net (code "67") (name "unconnected-(U1-PD3(INT1)-Pad5)") (class "Default")
      (node (ref "U1") (pin "5") (pinfunction "PD3(INT1)_5") (pintype "bidirectional"))
    )
    (net (code "68") (name "unconnected-(U1-PD7(AIN1)-Pad13)") (class "Default")
      (node (ref "U1") (pin "13") (pinfunction "PD7(AIN1)_13") (pintype "bidirectional"))
    )
    (net (code "69") (name "unconnected-(U5A-NULL1-Pad1)") (class "Default")
      (node (ref "U5") (pin "1") (pinfunction "NULL1_1") (pintype "bidirectional"))
    )
    (net (code "70") (name "unconnected-(U5A-NULL2-Pad5)") (class "Default")
      (node (ref "U5") (pin "5") (pinfunction "NULL2_5") (pintype "bidirectional"))
    )
    (net (code "71") (name "unconnected-(U6A-DIODE_BIAS-Pad2)") (class "Default")
      (node (ref "U6") (pin "2") (pinfunction "DIODE_BIAS_2") (pintype "bidirectional"))
    )
    (net (code "72") (name "unconnected-(U6B-DIODE_BIAS-Pad15)") (class "Default")
      (node (ref "U6") (pin "15") (pinfunction "DIODE_BIAS_15") (pintype "bidirectional"))
    )
    (net (code "73") (name "unconnected-(U7A-NULL1-Pad1)") (class "Default")
      (node (ref "U7") (pin "1") (pinfunction "NULL1_1") (pintype "bidirectional"))
    )
    (net (code "74") (name "unconnected-(U7A-NULL2-Pad5)") (class "Default")
      (node (ref "U7") (pin "5") (pinfunction "NULL2_5") (pintype "bidirectional"))
    )
    (net (code "75") (name "unconnected-(U8A-X-Pad13)") (class "Default")
      (node (ref "U8") (pin "13") (pinfunction "X_13") (pintype "bidirectional"))
    )
    (net (code "76") (name "unconnected-(U8A-X0-Pad12)") (class "Default")
      (node (ref "U8") (pin "12") (pinfunction "X0_12") (pintype "bidirectional"))
    )
    (net (code "77") (name "unconnected-(U8A-X1-Pad14)") (class "Default")
      (node (ref "U8") (pin "14") (pinfunction "X1_14") (pintype "bidirectional"))
    )
    (net (code "78") (name "unconnected-(U8A-X2-Pad15)") (class "Default")
      (node (ref "U8") (pin "15") (pinfunction "X2_15") (pintype "bidirectional"))
    )
    (net (code "79") (name "unconnected-(U8A-X3-Pad11)") (class "Default")
      (node (ref "U8") (pin "11") (pinfunction "X3_11") (pintype "bidirectional"))
    )
    (net (code "80") (name "unconnected-(U8A-Y0-Pad1)") (class "Default")
      (node (ref "U8") (pin "1") (pinfunction "Y0_1") (pintype "bidirectional"))
    )
    (net (code "81") (name "~{RESET}") (class "Default")
      (node (ref "J5") (pin "3") (pinfunction "3_3") (pintype "bidirectional"))
      (node (ref "R1") (pin "P$2") (pinfunction "2_P$2") (pintype "passive"))
      (node (ref "U1") (pin "1") (pinfunction "PC6(/RESET)_1") (pintype "bidirectional"))
    )
  )
)
